# mipi_serializer1.net
KiCad netlist of a schematic drawn in Altium Designer
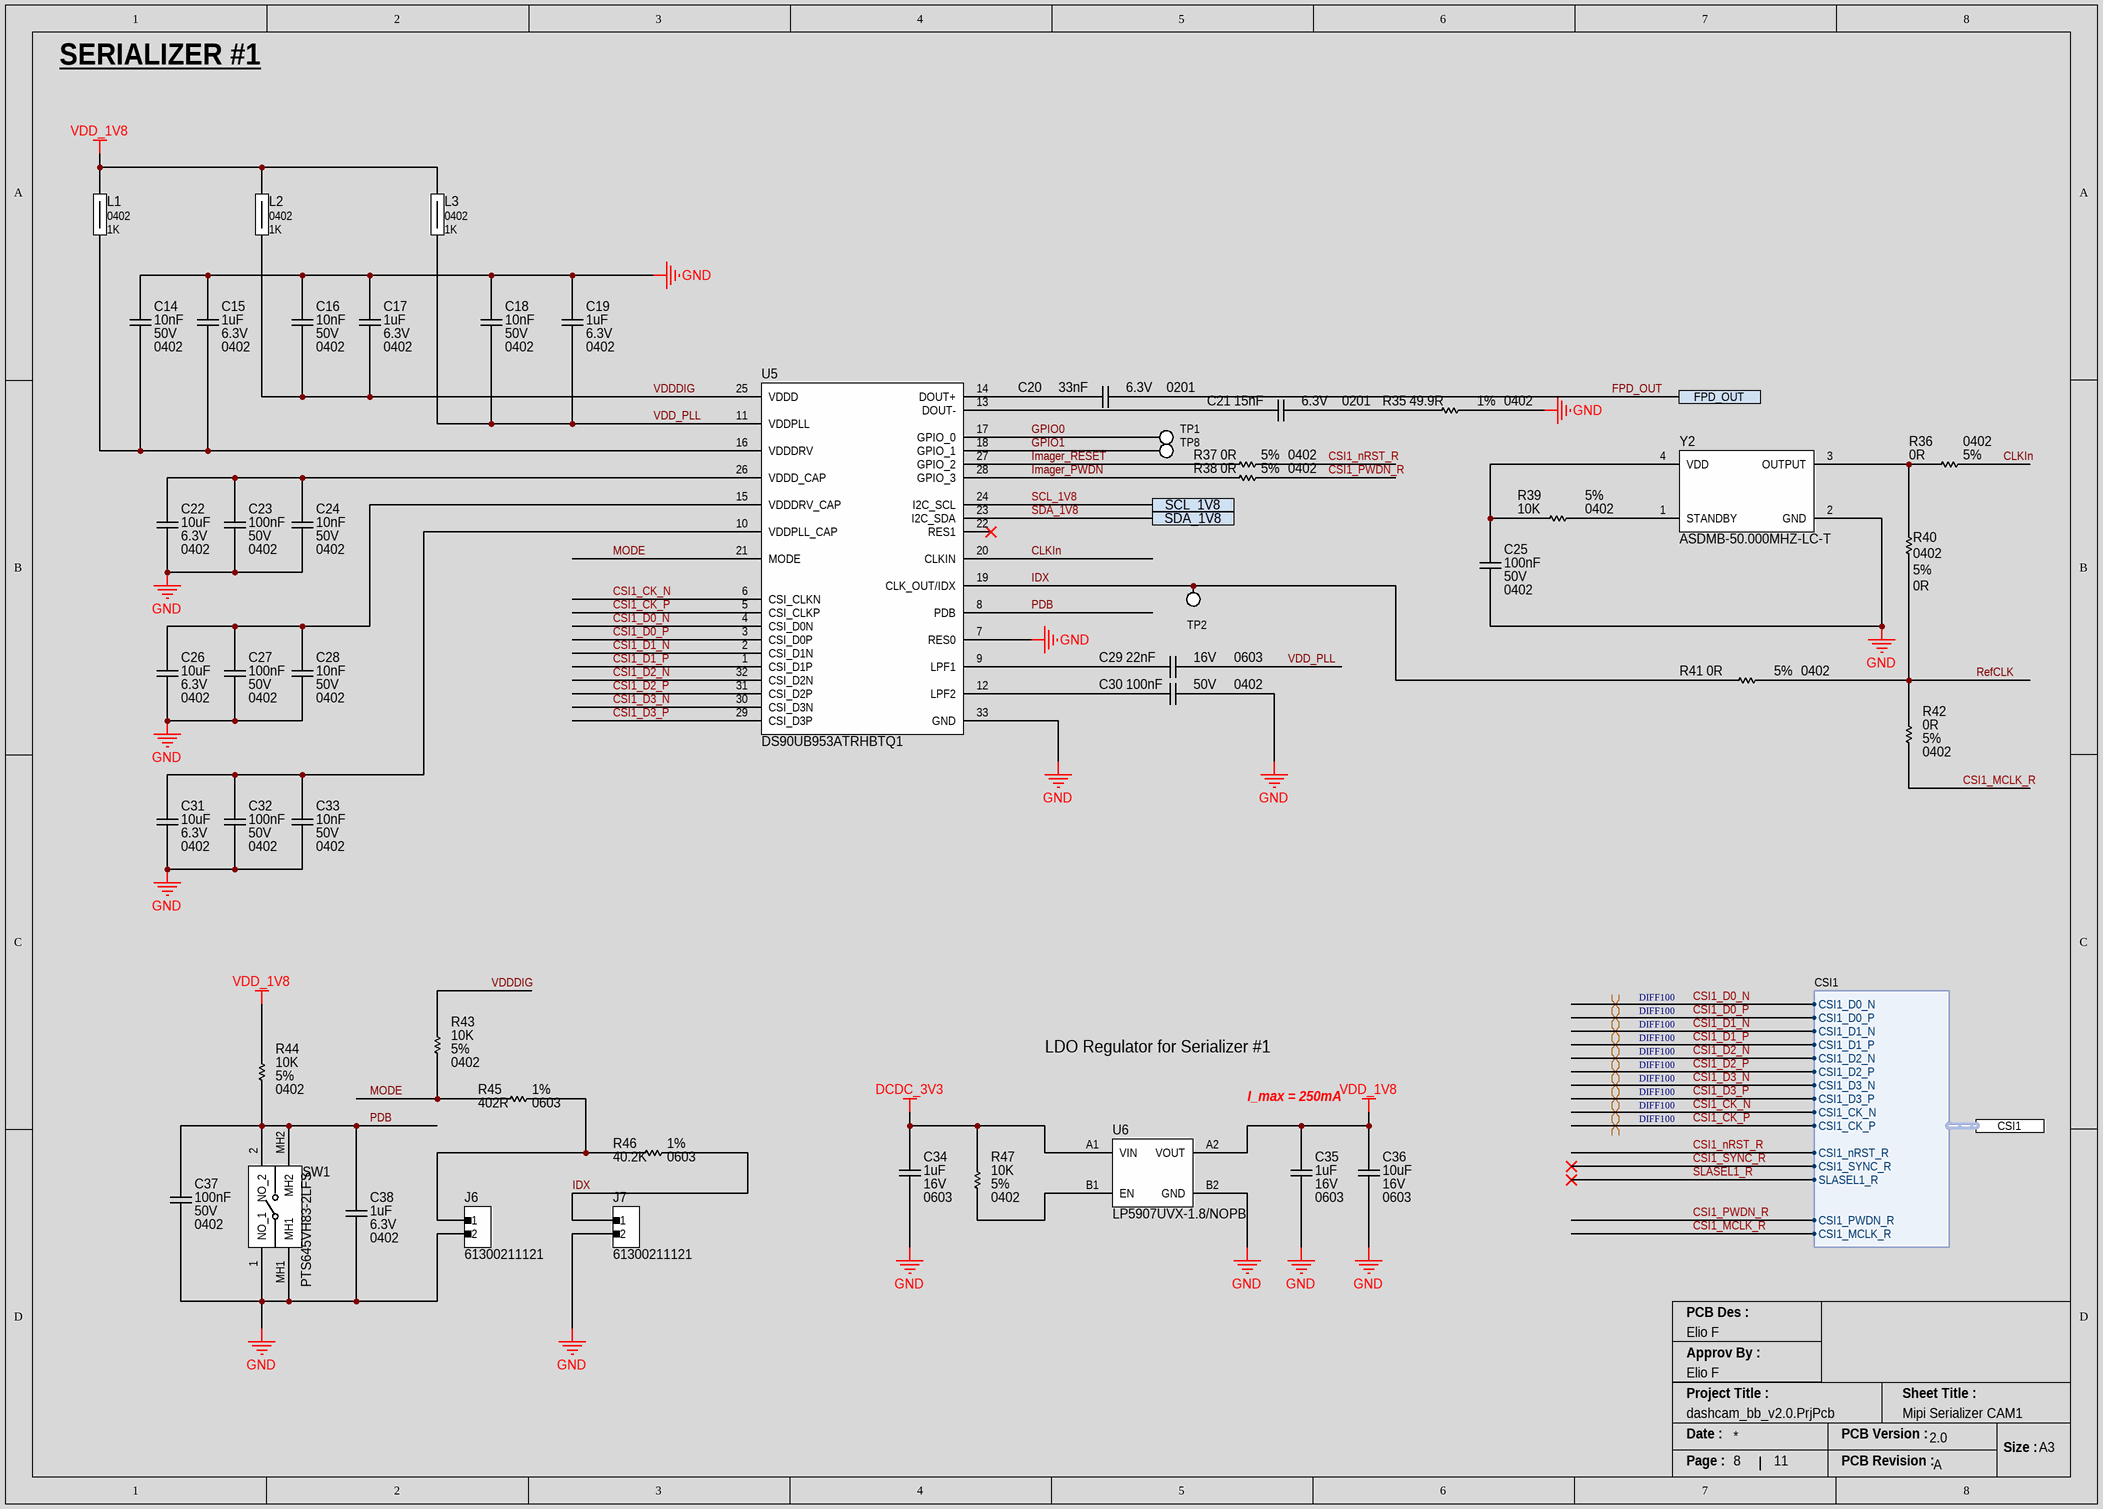
[diagram p0: mipi_serializer1.SchDoc]

(export (version "E")
  (design (tool "Eeschema 10.0.6"))
  (components
    (comp (ref "C14")
      (value "GRM155R71H103KA88D")
      (footprint "CAP_0402_CAPC1005X05N")
      (description "Multilayer Ceramic Capacitors MLCC Surface Mount 0402 0.01uF 50 Volts X7R 10%")
      (fields
        (field (name "MANUFACTURER") "Murata")
        (field (name "TOLERANCE") "10%")
        (field (name "VOLTAGE RATING") "50V")
        (field (name "CAPACITANCE") "10nF")
        (field (name "CASE/PACKAGE") "0402")
      )
      (libsource (lib "Electronic Devices_LIB") (part "CAP_10nF_50V_X7R_0402"))
    )
    (comp (ref "C15")
      (value "CL05B105KQ5NQNC")
      (footprint "CAP_0402_CAPC1005X05N")
      (description "Multilayer Ceramic Capacitor, 1 uF, 6.3 V, ï¿½ 10%, X7R, 0402 [1005 Metric]")
      (fields
        (field (name "MANUFACTURER") "Samsung")
        (field (name "TOLERANCE") "10%")
        (field (name "CAPACITANCE") "1uF")
        (field (name "VOLTAGE RATING") "6.3V")
        (field (name "CASE CODE (IMPERIAL)") "0402")
      )
      (libsource (lib "Electronic Devices_LIB") (part "CAP_1uF_6.3V_X7R_0402"))
    )
    (comp (ref "C16")
      (value "GRM155R71H103KA88D")
      (footprint "CAP_0402_CAPC1005X05N")
      (description "Multilayer Ceramic Capacitors MLCC Surface Mount 0402 0.01uF 50 Volts X7R 10%")
      (fields
        (field (name "MANUFACTURER") "Murata")
        (field (name "TOLERANCE") "10%")
        (field (name "VOLTAGE RATING") "50V")
        (field (name "CAPACITANCE") "10nF")
        (field (name "CASE/PACKAGE") "0402")
      )
      (libsource (lib "Electronic Devices_LIB") (part "CAP_10nF_50V_X7R_0402"))
    )
    (comp (ref "C17")
      (value "CL05B105KQ5NQNC")
      (footprint "CAP_0402_CAPC1005X05N")
      (description "Multilayer Ceramic Capacitor, 1 uF, 6.3 V, ï¿½ 10%, X7R, 0402 [1005 Metric]")
      (fields
        (field (name "MANUFACTURER") "Samsung")
        (field (name "TOLERANCE") "10%")
        (field (name "CAPACITANCE") "1uF")
        (field (name "VOLTAGE RATING") "6.3V")
        (field (name "CASE CODE (IMPERIAL)") "0402")
      )
      (libsource (lib "Electronic Devices_LIB") (part "CAP_1uF_6.3V_X7R_0402"))
    )
    (comp (ref "C18")
      (value "GRM155R71H103KA88D")
      (footprint "CAP_0402_CAPC1005X05N")
      (description "Multilayer Ceramic Capacitors MLCC Surface Mount 0402 0.01uF 50 Volts X7R 10%")
      (fields
        (field (name "MANUFACTURER") "Murata")
        (field (name "TOLERANCE") "10%")
        (field (name "VOLTAGE RATING") "50V")
        (field (name "CAPACITANCE") "10nF")
        (field (name "CASE/PACKAGE") "0402")
      )
      (libsource (lib "Electronic Devices_LIB") (part "CAP_10nF_50V_X7R_0402"))
    )
    (comp (ref "C19")
      (value "CL05B105KQ5NQNC")
      (footprint "CAP_0402_CAPC1005X05N")
      (description "Multilayer Ceramic Capacitor, 1 uF, 6.3 V, ï¿½ 10%, X7R, 0402 [1005 Metric]")
      (fields
        (field (name "MANUFACTURER") "Samsung")
        (field (name "TOLERANCE") "10%")
        (field (name "CAPACITANCE") "1uF")
        (field (name "VOLTAGE RATING") "6.3V")
        (field (name "CASE CODE (IMPERIAL)") "0402")
      )
      (libsource (lib "Electronic Devices_LIB") (part "CAP_1uF_6.3V_X7R_0402"))
    )
    (comp (ref "C20")
      (value "GRM033R60J333KE01D")
      (footprint "CAP_0201_CAPC0603X03N")
      (description "Multilayer Ceramic Capacitor, 0.033 uF, 6.3 V, ± 10%, X5R, 0201 [0603 Metric]")
      (fields
        (field (name "MANUFACTURER") "Murata")
        (field (name "TOLERANCE") "10%")
        (field (name "VOLTAGE RATING") "6.3V")
        (field (name "CAPACITANCE") "33nF")
        (field (name "CASE/PACKAGE") "0201")
      )
      (libsource (lib "Electronic Devices_LIB") (part "CAP_0.033uF_6.3V_X5R_0201"))
    )
    (comp (ref "C21")
      (value "GRM033R60J153KE01D")
      (footprint "CAP_0201_CAPC0603X03N")
      (description "0201 15 nF 6.3 V ±10% Tolerance X5R SMT Multilayer Ceramic Capacitor")
      (fields
        (field (name "MANUFACTURER") "Murata")
        (field (name "TOLERANCE") "10%")
        (field (name "VOLTAGE RATING") "6.3V")
        (field (name "CAPACITANCE") "15nF")
        (field (name "CASE/PACKAGE") "0201")
      )
      (libsource (lib "Electronic Devices_LIB") (part "CAP_0.015uF_6.3V_X5R_0201"))
    )
    (comp (ref "C22")
      (value "CL05A106MQ5NUNC")
      (footprint "CAP_0402_CAPC1005X05N")
      (description "Cap Ceramic 10uF 6.3V X5R 20% SMD 0402 85C T/R")
      (fields
        (field (name "MANUFACTURER") "Samsung")
        (field (name "TOLERANCE") "20%")
        (field (name "CASE/PACKAGE") "0402")
        (field (name "CAPACITANCE") "10uF")
        (field (name "VOLTAGE RATING") "6.3V")
      )
      (libsource (lib "Electronic Devices_LIB") (part "CAP_10UF_6.3V_X5R_0402"))
    )
    (comp (ref "C23")
      (value "GRM155R71H104KE14D")
      (footprint "CAP_0402_CAPC1005X05N")
      (description "Multilayer Ceramic Capacitor, 0.1 uF, 16 V, ± 10%, X7R, 0402 [1005 Metric]")
      (fields
        (field (name "MANUFACTURER") "Murata")
        (field (name "TOLERANCE") "10%")
        (field (name "VOLTAGE RATING") "50V")
        (field (name "CAPACITANCE") "100nF")
        (field (name "CASE/PACKAGE") "0402")
      )
      (libsource (lib "Electronic Devices_LIB") (part "CAP_100NF_50V_X7R_0402"))
    )
    (comp (ref "C24")
      (value "GRM155R71H103KA88D")
      (footprint "CAP_0402_CAPC1005X05N")
      (description "Multilayer Ceramic Capacitors MLCC Surface Mount 0402 0.01uF 50 Volts X7R 10%")
      (fields
        (field (name "MANUFACTURER") "Murata")
        (field (name "TOLERANCE") "10%")
        (field (name "VOLTAGE RATING") "50V")
        (field (name "CAPACITANCE") "10nF")
        (field (name "CASE/PACKAGE") "0402")
      )
      (libsource (lib "Electronic Devices_LIB") (part "CAP_10nF_50V_X7R_0402"))
    )
    (comp (ref "C25")
      (value "GRM155R71H104KE14D")
      (footprint "CAP_0402_CAPC1005X05N")
      (description "Multilayer Ceramic Capacitor, 0.1 uF, 16 V, ± 10%, X7R, 0402 [1005 Metric]")
      (fields
        (field (name "MANUFACTURER") "Murata")
        (field (name "TOLERANCE") "10%")
        (field (name "VOLTAGE RATING") "50V")
        (field (name "CAPACITANCE") "100nF")
        (field (name "CASE/PACKAGE") "0402")
      )
      (libsource (lib "Electronic Devices_LIB") (part "CAP_100NF_50V_X7R_0402"))
    )
    (comp (ref "C26")
      (value "CL05A106MQ5NUNC")
      (footprint "CAP_0402_CAPC1005X05N")
      (description "Cap Ceramic 10uF 6.3V X5R 20% SMD 0402 85C T/R")
      (fields
        (field (name "MANUFACTURER") "Samsung")
        (field (name "TOLERANCE") "20%")
        (field (name "CASE/PACKAGE") "0402")
        (field (name "CAPACITANCE") "10uF")
        (field (name "VOLTAGE RATING") "6.3V")
      )
      (libsource (lib "Electronic Devices_LIB") (part "CAP_10UF_6.3V_X5R_0402"))
    )
    (comp (ref "C27")
      (value "GRM155R71H104KE14D")
      (footprint "CAP_0402_CAPC1005X05N")
      (description "Multilayer Ceramic Capacitor, 0.1 uF, 16 V, ± 10%, X7R, 0402 [1005 Metric]")
      (fields
        (field (name "MANUFACTURER") "Murata")
        (field (name "TOLERANCE") "10%")
        (field (name "VOLTAGE RATING") "50V")
        (field (name "CAPACITANCE") "100nF")
        (field (name "CASE/PACKAGE") "0402")
      )
      (libsource (lib "Electronic Devices_LIB") (part "CAP_100NF_50V_X7R_0402"))
    )
    (comp (ref "C28")
      (value "GRM155R71H103KA88D")
      (footprint "CAP_0402_CAPC1005X05N")
      (description "Multilayer Ceramic Capacitors MLCC Surface Mount 0402 0.01uF 50 Volts X7R 10%")
      (fields
        (field (name "MANUFACTURER") "Murata")
        (field (name "TOLERANCE") "10%")
        (field (name "VOLTAGE RATING") "50V")
        (field (name "CAPACITANCE") "10nF")
        (field (name "CASE/PACKAGE") "0402")
      )
      (libsource (lib "Electronic Devices_LIB") (part "CAP_10nF_50V_X7R_0402"))
    )
    (comp (ref "C29")
      (value "C0603C223K4RACTU")
      (footprint "CAP_0603_CAPC1608X08N")
      (description "Multilayer Ceramic Capacitor, 0.022 uF, 16 V, ± 10%, X7R, 0603 [1608 Metric]")
      (fields
        (field (name "MANUFACTURER") "KEMET")
        (field (name "TOLERANCE") "10%")
        (field (name "VOLTAGE RATING (DC)") "16V")
        (field (name "CAPACITANCE") "22nF")
        (field (name "CASE/PACKAGE") "0603")
      )
      (libsource (lib "Electronic Devices_LIB") (part "CAP_22nF_16V_X7R_0603"))
    )
    (comp (ref "C30")
      (value "GRM155R71H104KE14D")
      (footprint "CAP_0402_CAPC1005X05N")
      (description "Multilayer Ceramic Capacitor, 0.1 uF, 16 V, ± 10%, X7R, 0402 [1005 Metric]")
      (fields
        (field (name "MANUFACTURER") "Murata")
        (field (name "TOLERANCE") "10%")
        (field (name "VOLTAGE RATING") "50V")
        (field (name "CAPACITANCE") "100nF")
        (field (name "CASE/PACKAGE") "0402")
      )
      (libsource (lib "Electronic Devices_LIB") (part "CAP_100NF_50V_X7R_0402"))
    )
    (comp (ref "C31")
      (value "CL05A106MQ5NUNC")
      (footprint "CAP_0402_CAPC1005X05N")
      (description "Cap Ceramic 10uF 6.3V X5R 20% SMD 0402 85C T/R")
      (fields
        (field (name "MANUFACTURER") "Samsung")
        (field (name "TOLERANCE") "20%")
        (field (name "CASE/PACKAGE") "0402")
        (field (name "CAPACITANCE") "10uF")
        (field (name "VOLTAGE RATING") "6.3V")
      )
      (libsource (lib "Electronic Devices_LIB") (part "CAP_10UF_6.3V_X5R_0402"))
    )
    (comp (ref "C32")
      (value "GRM155R71H104KE14D")
      (footprint "CAP_0402_CAPC1005X05N")
      (description "Multilayer Ceramic Capacitor, 0.1 uF, 16 V, ± 10%, X7R, 0402 [1005 Metric]")
      (fields
        (field (name "MANUFACTURER") "Murata")
        (field (name "TOLERANCE") "10%")
        (field (name "VOLTAGE RATING") "50V")
        (field (name "CAPACITANCE") "100nF")
        (field (name "CASE/PACKAGE") "0402")
      )
      (libsource (lib "Electronic Devices_LIB") (part "CAP_100NF_50V_X7R_0402"))
    )
    (comp (ref "C33")
      (value "GRM155R71H103KA88D")
      (footprint "CAP_0402_CAPC1005X05N")
      (description "Multilayer Ceramic Capacitors MLCC Surface Mount 0402 0.01uF 50 Volts X7R 10%")
      (fields
        (field (name "MANUFACTURER") "Murata")
        (field (name "TOLERANCE") "10%")
        (field (name "VOLTAGE RATING") "50V")
        (field (name "CAPACITANCE") "10nF")
        (field (name "CASE/PACKAGE") "0402")
      )
      (libsource (lib "Electronic Devices_LIB") (part "CAP_10nF_50V_X7R_0402"))
    )
    (comp (ref "C34")
      (value "CL10A105KO8NNNC")
      (footprint "CAP_0603_CAPC1608X08N")
      (description "CAP CER 1UF 16V X5R 0603")
      (fields
        (field (name "MANUFACTURER") "Samsung")
        (field (name "TOLERANCE") "10%")
        (field (name "VOLTAGE RATING") "16V")
        (field (name "CAPACITANCE") "1uF")
        (field (name "CASE/PACKAGE") "0603")
      )
      (libsource (lib "Electronic Devices_LIB") (part "CAP_1UF_16V_X5R_0603"))
    )
    (comp (ref "C35")
      (value "CL10A105KO8NNNC")
      (footprint "CAP_0603_CAPC1608X08N")
      (description "CAP CER 1UF 16V X5R 0603")
      (fields
        (field (name "MANUFACTURER") "Samsung")
        (field (name "TOLERANCE") "10%")
        (field (name "VOLTAGE RATING") "16V")
        (field (name "CAPACITANCE") "1uF")
        (field (name "CASE/PACKAGE") "0603")
      )
      (libsource (lib "Electronic Devices_LIB") (part "CAP_1UF_16V_X5R_0603"))
    )
    (comp (ref "C36")
      (value "GRM188R61C106MAALD")
      (footprint "CAP_0603_CAPC1608X08N")
      (description "0603 10 uF 16 V ±20% Tolerance X5R Multilayer Ceramic Chip Capacitor")
      (fields
        (field (name "MANUFACTURER") "Murata")
        (field (name "TOLERANCE") "20%")
        (field (name "VOLTAGE RATING") "16V")
        (field (name "CAPACITANCE") "10uF")
        (field (name "CASE/PACKAGE") "0603")
      )
      (libsource (lib "Electronic Devices_LIB") (part "CAP_10UF_16V_X5R_0603"))
    )
    (comp (ref "C37")
      (value "GRM155R71H104KE14D")
      (footprint "CAP_0402_CAPC1005X05N")
      (description "Multilayer Ceramic Capacitor, 0.1 uF, 16 V, ± 10%, X7R, 0402 [1005 Metric]")
      (fields
        (field (name "MANUFACTURER") "Murata")
        (field (name "TOLERANCE") "10%")
        (field (name "VOLTAGE RATING") "50V")
        (field (name "CAPACITANCE") "100nF")
        (field (name "CASE/PACKAGE") "0402")
      )
      (libsource (lib "Electronic Devices_LIB") (part "CAP_100NF_50V_X7R_0402"))
    )
    (comp (ref "C38")
      (value "CL05B105KQ5NQNC")
      (footprint "CAP_0402_CAPC1005X05N")
      (description "Multilayer Ceramic Capacitor, 1 uF, 6.3 V, ï¿½ 10%, X7R, 0402 [1005 Metric]")
      (fields
        (field (name "MANUFACTURER") "Samsung")
        (field (name "TOLERANCE") "10%")
        (field (name "CAPACITANCE") "1uF")
        (field (name "VOLTAGE RATING") "6.3V")
        (field (name "CASE CODE (IMPERIAL)") "0402")
      )
      (libsource (lib "Electronic Devices_LIB") (part "CAP_1uF_6.3V_X7R_0402"))
    )
    (comp (ref "J6")
      (value "61300211121")
      (footprint "HEADER_MALE_HDRV2W110P0X254_1X2_508X254X854P")
      (description "THT Vertical Pin Header WR-PHD, Pitch 2.54 mm, Single Row, 2 pins")
      (fields (field (name "MANUFACTURER") "Wurth Electronics"))
      (libsource (lib "Electronic Devices_LIB") (part "CONN_HEADER_MALE_2P_2.54_61300211121"))
    )
    (comp (ref "J7")
      (value "61300211121")
      (footprint "HEADER_MALE_HDRV2W110P0X254_1X2_508X254X854P")
      (description "THT Vertical Pin Header WR-PHD, Pitch 2.54 mm, Single Row, 2 pins")
      (fields (field (name "MANUFACTURER") "Wurth Electronics"))
      (libsource (lib "Electronic Devices_LIB") (part "CONN_HEADER_MALE_2P_2.54_61300211121"))
    )
    (comp (ref "L1")
      (value "*BLM15AX102SN1D")
      (footprint "IND_0402")
      (description "Ferrite Beads Multi-Layer 1KOhm 25% 100MHz 350mA 490mOhm DCR 0402 Paper T/R")
      (fields
        (field (name "MANUFACTURER") "Murata")
        (field (name "MANUFACTURER PART NUMBER") "BLM15AX102SN1D")
        (field (name "CASE/PACKAGE") "0402")
        (field (name "IMPEDANCE") "1K")
      )
      (libsource (lib "Electronic Devices_LIB") (part "IND_FERRITE_BEADS_1K_350mA_BLM15AX102SN1D"))
    )
    (comp (ref "L2")
      (value "*BLM15AX102SN1D")
      (footprint "IND_0402")
      (description "Ferrite Beads Multi-Layer 1KOhm 25% 100MHz 350mA 490mOhm DCR 0402 Paper T/R")
      (fields
        (field (name "MANUFACTURER") "Murata")
        (field (name "MANUFACTURER PART NUMBER") "BLM15AX102SN1D")
        (field (name "CASE/PACKAGE") "0402")
        (field (name "IMPEDANCE") "1K")
      )
      (libsource (lib "Electronic Devices_LIB") (part "IND_FERRITE_BEADS_1K_350mA_BLM15AX102SN1D"))
    )
    (comp (ref "L3")
      (value "*BLM15AX102SN1D")
      (footprint "IND_0402")
      (description "Ferrite Beads Multi-Layer 1KOhm 25% 100MHz 350mA 490mOhm DCR 0402 Paper T/R")
      (fields
        (field (name "MANUFACTURER") "Murata")
        (field (name "MANUFACTURER PART NUMBER") "BLM15AX102SN1D")
        (field (name "CASE/PACKAGE") "0402")
        (field (name "IMPEDANCE") "1K")
      )
      (libsource (lib "Electronic Devices_LIB") (part "IND_FERRITE_BEADS_1K_350mA_BLM15AX102SN1D"))
    )
    (comp (ref "R35")
      (value "CR0402-FX-49R9GLF")
      (footprint "RES_0402_RESC1005X04N")
      (description "SMD Chip Resistor, 49.9 Ohm, ± 1%, 63 mW, 0402 [1005 Metric], Thick Film, General Purpose")
      (fields
        (field (name "MANUFACTURER") "Bourns")
        (field (name "RESISTANCE") "49.9R")
        (field (name "TOLERANCE") "1%")
        (field (name "CASE/PACKAGE") "0402")
      )
      (libsource (lib "Electronic Devices_LIB") (part "RES_49.9R_1%_63mW_0402"))
    )
    (comp (ref "R36")
      (value "ERJ-2GE0R00X")
      (footprint "RES_0402_RESC1005X04N")
      (description "SMD Chip Resistor, Jumper, 0 ohm, 100 mW, 0402 [1005 Metric], Thick Film, General Purpose")
      (fields
        (field (name "MANUFACTURER") "Panasonic")
        (field (name "CASE CODE (IMPERIAL)") "0402")
        (field (name "TOLERANCE") "5%")
        (field (name "RESISTANCE") "0R")
      )
      (libsource (lib "Electronic Devices_LIB") (part "RES_0R_5%_100mW_0402"))
    )
    (comp (ref "R37")
      (value "ERJ-2GE0R00X")
      (footprint "RES_0402_RESC1005X04N")
      (description "SMD Chip Resistor, Jumper, 0 ohm, 100 mW, 0402 [1005 Metric], Thick Film, General Purpose")
      (fields
        (field (name "MANUFACTURER") "Panasonic")
        (field (name "CASE CODE (IMPERIAL)") "0402")
        (field (name "TOLERANCE") "5%")
        (field (name "RESISTANCE") "0R")
      )
      (libsource (lib "Electronic Devices_LIB") (part "RES_0R_5%_100mW_0402"))
    )
    (comp (ref "R38")
      (value "ERJ-2GE0R00X")
      (footprint "RES_0402_RESC1005X04N")
      (description "SMD Chip Resistor, Jumper, 0 ohm, 100 mW, 0402 [1005 Metric], Thick Film, General Purpose")
      (fields
        (field (name "MANUFACTURER") "Panasonic")
        (field (name "CASE CODE (IMPERIAL)") "0402")
        (field (name "TOLERANCE") "5%")
        (field (name "RESISTANCE") "0R")
      )
      (libsource (lib "Electronic Devices_LIB") (part "RES_0R_5%_100mW_0402"))
    )
    (comp (ref "R39")
      (value "ERJ-2GEJ103X")
      (footprint "RES_0402_RESC1005X04N")
      (description "Res Thick Film 0402 10K Ohm 5% 1/10W ±200ppm/°C Molded SMD Punched Carrier T/R")
      (fields
        (field (name "MANUFACTURER") "Panasonic")
        (field (name "TOLERANCE") "5%")
        (field (name "RESISTANCE") "10K")
        (field (name "CASE/PACKAGE") "0402")
      )
      (libsource (lib "Electronic Devices_LIB") (part "RES_10K_5%_100mW_0402"))
    )
    (comp (ref "R40")
      (value "ERJ-2GE0R00X")
      (footprint "RES_0402_RESC1005X04N")
      (description "SMD Chip Resistor, Jumper, 0 ohm, 100 mW, 0402 [1005 Metric], Thick Film, General Purpose")
      (fields
        (field (name "MANUFACTURER") "Panasonic")
        (field (name "CASE CODE (IMPERIAL)") "0402")
        (field (name "TOLERANCE") "5%")
        (field (name "RESISTANCE") "0R")
      )
      (libsource (lib "Electronic Devices_LIB") (part "RES_0R_5%_100mW_0402"))
    )
    (comp (ref "R41")
      (value "ERJ-2GE0R00X")
      (footprint "RES_0402_RESC1005X04N")
      (description "SMD Chip Resistor, Jumper, 0 ohm, 100 mW, 0402 [1005 Metric], Thick Film, General Purpose")
      (fields
        (field (name "MANUFACTURER") "Panasonic")
        (field (name "CASE CODE (IMPERIAL)") "0402")
        (field (name "TOLERANCE") "5%")
        (field (name "RESISTANCE") "0R")
      )
      (libsource (lib "Electronic Devices_LIB") (part "RES_0R_5%_100mW_0402"))
    )
    (comp (ref "R42")
      (value "ERJ-2GE0R00X")
      (footprint "RES_0402_RESC1005X04N")
      (description "SMD Chip Resistor, Jumper, 0 ohm, 100 mW, 0402 [1005 Metric], Thick Film, General Purpose")
      (fields
        (field (name "MANUFACTURER") "Panasonic")
        (field (name "CASE CODE (IMPERIAL)") "0402")
        (field (name "TOLERANCE") "5%")
        (field (name "RESISTANCE") "0R")
      )
      (libsource (lib "Electronic Devices_LIB") (part "RES_0R_5%_100mW_0402"))
    )
    (comp (ref "R43")
      (value "ERJ-2GEJ103X")
      (footprint "RES_0402_RESC1005X04N")
      (description "Res Thick Film 0402 10K Ohm 5% 1/10W ±200ppm/°C Molded SMD Punched Carrier T/R")
      (fields
        (field (name "MANUFACTURER") "Panasonic")
        (field (name "TOLERANCE") "5%")
        (field (name "RESISTANCE") "10K")
        (field (name "CASE/PACKAGE") "0402")
      )
      (libsource (lib "Electronic Devices_LIB") (part "RES_10K_5%_100mW_0402"))
    )
    (comp (ref "R44")
      (value "ERJ-2GEJ103X")
      (footprint "RES_0402_RESC1005X04N")
      (description "Res Thick Film 0402 10K Ohm 5% 1/10W ±200ppm/°C Molded SMD Punched Carrier T/R")
      (fields
        (field (name "MANUFACTURER") "Panasonic")
        (field (name "TOLERANCE") "5%")
        (field (name "RESISTANCE") "10K")
        (field (name "CASE/PACKAGE") "0402")
      )
      (libsource (lib "Electronic Devices_LIB") (part "RES_10K_5%_100mW_0402"))
    )
    (comp (ref "R45")
      (value "CRCW0603402RFKEA")
      (footprint "RES_0603_RESC1608X04N")
      (description "CRCW Series 0603 0.1 W 402 Ohm ±1 % ±100 ppm/K SMT Thick Film Chip Resistor")
      (fields
        (field (name "MANUFACTURER") "Vishay")
        (field (name "TOLERANCE") "1%")
        (field (name "RESISTANCE") "402R")
        (field (name "CASE/PACKAGE") "0603")
      )
      (libsource (lib "Electronic Devices_LIB") (part "RES_402R_1%_100mW_0402"))
    )
    (comp (ref "R46")
      (value "RC0603FR-0740K2L")
      (footprint "RES_0603_RESC1608X04N")
      (description "Res General Purpose Thick Film 0603 40.2K Ohm 1% 1/10W ±100ppm/°C Molded SMD Paper T/R")
      (fields
        (field (name "MANUFACTURER") "Yageo")
        (field (name "TOLERANCE") "1%")
        (field (name "RESISTANCE") "40.2K")
        (field (name "CASE/PACKAGE") "0603")
      )
      (libsource (lib "Electronic Devices_LIB") (part "RES_40.2K_1%_100mW_0603"))
    )
    (comp (ref "R47")
      (value "ERJ-2GEJ103X")
      (footprint "RES_0402_RESC1005X04N")
      (description "Res Thick Film 0402 10K Ohm 5% 1/10W ±200ppm/°C Molded SMD Punched Carrier T/R")
      (fields
        (field (name "MANUFACTURER") "Panasonic")
        (field (name "TOLERANCE") "5%")
        (field (name "RESISTANCE") "10K")
        (field (name "CASE/PACKAGE") "0402")
      )
      (libsource (lib "Electronic Devices_LIB") (part "RES_10K_5%_100mW_0402"))
    )
    (comp (ref "SW1")
      (value "PTS645VH83-2LFS")
      (footprint "SW_RA_PTS645VH832LFS")
      (description "Switch Tactile N.O SPST Round Button PC Pins 0.05A 12VDC 100000Cycle 1.96N Thru-Hole Bulk")
      (fields (field (name "MANUFACTURER") "ITT C&K"))
      (libsource (lib "Electronic Devices_LIB") (part "SWITCH_SPST_NO_RA_PTS645VH83-2LFS"))
    )
    (comp (ref "TP1")
      (value "NO COMPONENT")
      (footprint "TP_PAD_1.6MM_SMD_ROUND")
      (description "Test Point, SMD pad, round, 1.5mm, 1.6mm, 3mm diameter")
      (libsource (lib "Electronic Devices_LIB") (part "TP_PAD_SMD_Round"))
    )
    (comp (ref "TP2")
      (value "NO COMPONENT")
      (footprint "TP_PAD_1.6MM_SMD_ROUND")
      (description "Test Point, SMD pad, round, 1.5mm, 1.6mm, 3mm diameter")
      (libsource (lib "Electronic Devices_LIB") (part "TP_PAD_SMD_Round"))
    )
    (comp (ref "TP8")
      (value "NO COMPONENT")
      (footprint "TP_PAD_1.6MM_SMD_ROUND")
      (description "Test Point, SMD pad, round, 1.5mm, 1.6mm, 3mm diameter")
      (libsource (lib "Electronic Devices_LIB") (part "TP_PAD_SMD_Round"))
    )
    (comp (ref "U5")
      (value "DS90UB953ATRHBTQ1")
      (footprint "IC_SERIALIZER_QFN50P500X500X100-33N-D")
      (description "FPD-Link III 4.16-Gbps serializer with CSI-2 interface 32-VQFN -40 to 125")
      (fields (field (name "MANUFACTURER") "Texas Instruments"))
      (libsource (lib "Electronic Devices_LIB") (part "IC_MIPI_SERIALIZER_DS90UB953ATRHBTQ1"))
    )
    (comp (ref "U6")
      (value "LP5907UVX-1.8/NOPB")
      (footprint "IC_REG_LDO_BGA4C35P2X2_71X71X40")
      (description "Low Dropout Regulators(LDO) Positive Fixed 200mV @ 250mA 5.5V 1.8V 250mA DSBGA-4 RoHS")
      (fields (field (name "MANUFACTURER") "Texas Instruments"))
      (libsource (lib "Electronic Devices_LIB") (part "IC_REG_LDO_1.8V_250mA_LP5907UVX-1.8/NOPB"))
    )
    (comp (ref "Y2")
      (value "ASDMB-50.000MHZ-LC-T")
      (footprint "XTAL_ASDMB-50.000MHZ-LC-T")
      (fields (field (name "MANUFACTURER") "Abracon"))
      (libsource (lib "Electronic Devices_LIB") (part "CRYSTAL_ABRACON_50MHz_ASDMB-50.000MHZ-LC-T"))
    )
  )
  (nets
    (net (code "2") (name "/CLKIn") (class "Default")
      (node (ref "R36") (pin "2") (pinfunction "2_2") (pintype "passive"))
      (node (ref "U5") (pin "20") (pinfunction "CLKIN_20") (pintype "passive"))
    )
    (net (code "3") (name "/CSI1_CK_N") (class "Default")
      (node (ref "U5") (pin "6") (pinfunction "CSI_CLKN_6") (pintype "passive"))
    )
    (net (code "4") (name "/CSI1_CK_P") (class "Default")
      (node (ref "U5") (pin "5") (pinfunction "CSI_CLKP_5") (pintype "passive"))
    )
    (net (code "5") (name "/CSI1_D0_N") (class "Default")
      (node (ref "U5") (pin "4") (pinfunction "CSI_D0N_4") (pintype "passive"))
    )
    (net (code "6") (name "/CSI1_D0_P") (class "Default")
      (node (ref "U5") (pin "3") (pinfunction "CSI_D0P_3") (pintype "passive"))
    )
    (net (code "7") (name "/CSI1_D1_N") (class "Default")
      (node (ref "U5") (pin "2") (pinfunction "CSI_D1N_2") (pintype "passive"))
    )
    (net (code "8") (name "/CSI1_D1_P") (class "Default")
      (node (ref "U5") (pin "1") (pinfunction "CSI_D1P_1") (pintype "passive"))
    )
    (net (code "9") (name "/CSI1_D2_N") (class "Default")
      (node (ref "U5") (pin "32") (pinfunction "CSI_D2N_32") (pintype "passive"))
    )
    (net (code "10") (name "/CSI1_D2_P") (class "Default")
      (node (ref "U5") (pin "31") (pinfunction "CSI_D2P_31") (pintype "passive"))
    )
    (net (code "11") (name "/CSI1_D3_N") (class "Default")
      (node (ref "U5") (pin "30") (pinfunction "CSI_D3N_30") (pintype "passive"))
    )
    (net (code "12") (name "/CSI1_D3_P") (class "Default")
      (node (ref "U5") (pin "29") (pinfunction "CSI_D3P_29") (pintype "passive"))
    )
    (net (code "13") (name "/CSI1_MCLK_R") (class "Default")
      (node (ref "R42") (pin "1") (pinfunction "1_1") (pintype "passive"))
    )
    (net (code "14") (name "/CSI1_PWDN_R") (class "Default")
      (node (ref "R38") (pin "2") (pinfunction "2_2") (pintype "passive"))
    )
    (net (code "16") (name "/CSI1_nRST_R") (class "Default")
      (node (ref "R37") (pin "2") (pinfunction "2_2") (pintype "passive"))
    )
    (net (code "17") (name "/FPD_OUT") (class "Default")
      (node (ref "C20") (pin "2") (pinfunction "2_2") (pintype "passive"))
    )
    (net (code "18") (name "/GPIO0") (class "Default")
      (node (ref "TP1") (pin "1") (pinfunction "1_1") (pintype "passive"))
      (node (ref "U5") (pin "17") (pinfunction "GPIO_0_17") (pintype "passive"))
    )
    (net (code "19") (name "/GPIO1") (class "Default")
      (node (ref "TP8") (pin "1") (pinfunction "1_1") (pintype "passive"))
      (node (ref "U5") (pin "18") (pinfunction "GPIO_1_18") (pintype "passive"))
    )
    (net (code "20") (name "/IDX") (class "Default")
      (node (ref "J7") (pin "1") (pinfunction "1_1") (pintype "passive"))
      (node (ref "R41") (pin "2") (pinfunction "2_2") (pintype "passive"))
      (node (ref "R46") (pin "2") (pinfunction "2_2") (pintype "passive"))
      (node (ref "TP2") (pin "1") (pinfunction "1_1") (pintype "passive"))
      (node (ref "U5") (pin "19") (pinfunction "CLK_OUT/IDX_19") (pintype "passive"))
    )
    (net (code "21") (name "/Imager_PWDN") (class "Default")
      (node (ref "R38") (pin "1") (pinfunction "1_1") (pintype "passive"))
      (node (ref "U5") (pin "28") (pinfunction "GPIO_3_28") (pintype "passive"))
    )
    (net (code "22") (name "/Imager_RESET") (class "Default")
      (node (ref "R37") (pin "1") (pinfunction "1_1") (pintype "passive"))
      (node (ref "U5") (pin "27") (pinfunction "GPIO_2_27") (pintype "passive"))
    )
    (net (code "23") (name "/MODE") (class "Default")
      (node (ref "R43") (pin "1") (pinfunction "1_1") (pintype "passive"))
      (node (ref "R45") (pin "1") (pinfunction "1_1") (pintype "passive"))
      (node (ref "U5") (pin "21") (pinfunction "MODE_21") (pintype "passive"))
    )
    (net (code "24") (name "/PDB") (class "Default")
      (node (ref "C37") (pin "2") (pinfunction "2_2") (pintype "passive"))
      (node (ref "C38") (pin "2") (pinfunction "2_2") (pintype "passive"))
      (node (ref "R44") (pin "1") (pinfunction "1_1") (pintype "passive"))
      (node (ref "SW1") (pin "2") (pinfunction "NO_2_2") (pintype "passive"))
      (node (ref "SW1") (pin "MH2") (pinfunction "MH2_MH2") (pintype "passive"))
      (node (ref "U5") (pin "8") (pinfunction "PDB_8") (pintype "passive"))
    )
    (net (code "25") (name "/RefCLK") (class "Default")
      (node (ref "R40") (pin "1") (pinfunction "1_1") (pintype "passive"))
      (node (ref "R41") (pin "1") (pinfunction "1_1") (pintype "passive"))
      (node (ref "R42") (pin "2") (pinfunction "2_2") (pintype "passive"))
    )
    (net (code "26") (name "/SCL_1V8") (class "Default")
      (node (ref "U5") (pin "24") (pinfunction "I2C_SCL_24") (pintype "passive"))
    )
    (net (code "27") (name "/SDA_1V8") (class "Default")
      (node (ref "U5") (pin "23") (pinfunction "I2C_SDA_23") (pintype "passive"))
    )
    (net (code "29") (name "/VDDDIG") (class "Default")
      (node (ref "C16") (pin "1") (pinfunction "1_1") (pintype "passive"))
      (node (ref "C17") (pin "1") (pinfunction "1_1") (pintype "passive"))
      (node (ref "L2") (pin "1") (pinfunction "1_1") (pintype "passive"))
      (node (ref "R43") (pin "2") (pinfunction "2_2") (pintype "passive"))
      (node (ref "U5") (pin "25") (pinfunction "VDDD_25") (pintype "passive"))
    )
    (net (code "30") (name "/VDD_PLL") (class "Default")
      (node (ref "C18") (pin "1") (pinfunction "1_1") (pintype "passive"))
      (node (ref "C19") (pin "1") (pinfunction "1_1") (pintype "passive"))
      (node (ref "C29") (pin "2") (pinfunction "2_2") (pintype "passive"))
      (node (ref "L3") (pin "1") (pinfunction "1_1") (pintype "passive"))
      (node (ref "U5") (pin "11") (pinfunction "VDDPLL_11") (pintype "passive"))
    )
    (net (code "32") (name "DCDC_3V3") (class "Default")
      (node (ref "C34") (pin "2") (pinfunction "2_2") (pintype "passive"))
      (node (ref "R47") (pin "2") (pinfunction "2_2") (pintype "passive"))
      (node (ref "U6") (pin "A1") (pinfunction "VIN_A1") (pintype "passive"))
    )
    (net (code "33") (name "GND") (class "Default")
      (node (ref "C14") (pin "2") (pinfunction "2_2") (pintype "passive"))
      (node (ref "C15") (pin "2") (pinfunction "2_2") (pintype "passive"))
      (node (ref "C16") (pin "2") (pinfunction "2_2") (pintype "passive"))
      (node (ref "C17") (pin "2") (pinfunction "2_2") (pintype "passive"))
      (node (ref "C18") (pin "2") (pinfunction "2_2") (pintype "passive"))
      (node (ref "C19") (pin "2") (pinfunction "2_2") (pintype "passive"))
      (node (ref "C22") (pin "1") (pinfunction "1_1") (pintype "passive"))
      (node (ref "C23") (pin "1") (pinfunction "1_1") (pintype "passive"))
      (node (ref "C24") (pin "1") (pinfunction "1_1") (pintype "passive"))
      (node (ref "C25") (pin "1") (pinfunction "1_1") (pintype "passive"))
      (node (ref "C26") (pin "1") (pinfunction "1_1") (pintype "passive"))
      (node (ref "C27") (pin "1") (pinfunction "1_1") (pintype "passive"))
      (node (ref "C28") (pin "1") (pinfunction "1_1") (pintype "passive"))
      (node (ref "C30") (pin "1") (pinfunction "1_1") (pintype "passive"))
      (node (ref "C31") (pin "1") (pinfunction "1_1") (pintype "passive"))
      (node (ref "C32") (pin "1") (pinfunction "1_1") (pintype "passive"))
      (node (ref "C33") (pin "1") (pinfunction "1_1") (pintype "passive"))
      (node (ref "C34") (pin "1") (pinfunction "1_1") (pintype "passive"))
      (node (ref "C35") (pin "1") (pinfunction "1_1") (pintype "passive"))
      (node (ref "C36") (pin "1") (pinfunction "1_1") (pintype "passive"))
      (node (ref "C37") (pin "1") (pinfunction "1_1") (pintype "passive"))
      (node (ref "C38") (pin "1") (pinfunction "1_1") (pintype "passive"))
      (node (ref "J6") (pin "2") (pinfunction "2_2") (pintype "passive"))
      (node (ref "J7") (pin "2") (pinfunction "2_2") (pintype "passive"))
      (node (ref "R35") (pin "2") (pinfunction "2_2") (pintype "passive"))
      (node (ref "SW1") (pin "1") (pinfunction "NO_1_1") (pintype "passive"))
      (node (ref "SW1") (pin "MH1") (pinfunction "MH1_MH1") (pintype "passive"))
      (node (ref "U5") (pin "33") (pinfunction "GND_33") (pintype "passive"))
      (node (ref "U5") (pin "7") (pinfunction "RES0_7") (pintype "passive"))
      (node (ref "U6") (pin "B2") (pinfunction "GND_B2") (pintype "passive"))
      (node (ref "Y2") (pin "2") (pinfunction "GND_2") (pintype "power_in"))
    )
    (net (code "34") (name "Net-(C21-Pad2)") (class "Default")
      (node (ref "C21") (pin "2") (pinfunction "2_2") (pintype "passive"))
      (node (ref "R35") (pin "1") (pinfunction "1_1") (pintype "passive"))
    )
    (net (code "35") (name "Net-(J6-Pad1)") (class "Default")
      (node (ref "J6") (pin "1") (pinfunction "1_1") (pintype "passive"))
      (node (ref "R45") (pin "2") (pinfunction "2_2") (pintype "passive"))
      (node (ref "R46") (pin "1") (pinfunction "1_1") (pintype "passive"))
    )
    (net (code "36") (name "Net-(U5-DOUT+)") (class "Default")
      (node (ref "C20") (pin "1") (pinfunction "1_1") (pintype "passive"))
      (node (ref "U5") (pin "14") (pinfunction "DOUT+_14") (pintype "passive"))
    )
    (net (code "37") (name "Net-(U5-DOUT-)") (class "Default")
      (node (ref "C21") (pin "1") (pinfunction "1_1") (pintype "passive"))
      (node (ref "U5") (pin "13") (pinfunction "DOUT-_13") (pintype "passive"))
    )
    (net (code "38") (name "Net-(U5-LPF1)") (class "Default")
      (node (ref "C29") (pin "1") (pinfunction "1_1") (pintype "passive"))
      (node (ref "U5") (pin "9") (pinfunction "LPF1_9") (pintype "passive"))
    )
    (net (code "39") (name "Net-(U5-LPF2)") (class "Default")
      (node (ref "C30") (pin "2") (pinfunction "2_2") (pintype "passive"))
      (node (ref "U5") (pin "12") (pinfunction "LPF2_12") (pintype "passive"))
    )
    (net (code "40") (name "Net-(U5-VDDDRV)") (class "Default")
      (node (ref "C14") (pin "1") (pinfunction "1_1") (pintype "passive"))
      (node (ref "C15") (pin "1") (pinfunction "1_1") (pintype "passive"))
      (node (ref "L1") (pin "1") (pinfunction "1_1") (pintype "passive"))
      (node (ref "U5") (pin "16") (pinfunction "VDDDRV_16") (pintype "passive"))
    )
    (net (code "41") (name "Net-(U5-VDDDRV_CAP)") (class "Default")
      (node (ref "C26") (pin "2") (pinfunction "2_2") (pintype "passive"))
      (node (ref "C27") (pin "2") (pinfunction "2_2") (pintype "passive"))
      (node (ref "C28") (pin "2") (pinfunction "2_2") (pintype "passive"))
      (node (ref "U5") (pin "15") (pinfunction "VDDDRV_CAP_15") (pintype "passive"))
    )
    (net (code "42") (name "Net-(U5-VDDD_CAP)") (class "Default")
      (node (ref "C22") (pin "2") (pinfunction "2_2") (pintype "passive"))
      (node (ref "C23") (pin "2") (pinfunction "2_2") (pintype "passive"))
      (node (ref "C24") (pin "2") (pinfunction "2_2") (pintype "passive"))
      (node (ref "U5") (pin "26") (pinfunction "VDDD_CAP_26") (pintype "passive"))
    )
    (net (code "43") (name "Net-(U5-VDDPLL_CAP)") (class "Default")
      (node (ref "C31") (pin "2") (pinfunction "2_2") (pintype "passive"))
      (node (ref "C32") (pin "2") (pinfunction "2_2") (pintype "passive"))
      (node (ref "C33") (pin "2") (pinfunction "2_2") (pintype "passive"))
      (node (ref "U5") (pin "10") (pinfunction "VDDPLL_CAP_10") (pintype "passive"))
    )
    (net (code "44") (name "Net-(U6-EN)") (class "Default")
      (node (ref "R47") (pin "1") (pinfunction "1_1") (pintype "passive"))
      (node (ref "U6") (pin "B1") (pinfunction "EN_B1") (pintype "passive"))
    )
    (net (code "45") (name "Net-(Y2-OUTPUT)") (class "Default")
      (node (ref "R36") (pin "1") (pinfunction "1_1") (pintype "passive"))
      (node (ref "R40") (pin "2") (pinfunction "2_2") (pintype "passive"))
      (node (ref "Y2") (pin "3") (pinfunction "OUTPUT_3") (pintype "passive"))
    )
    (net (code "46") (name "Net-(Y2-STANDBY)") (class "Default")
      (node (ref "R39") (pin "2") (pinfunction "2_2") (pintype "passive"))
      (node (ref "Y2") (pin "1") (pinfunction "STANDBY_1") (pintype "passive"))
    )
    (net (code "47") (name "Net-(Y2-VDD)") (class "Default")
      (node (ref "C25") (pin "2") (pinfunction "2_2") (pintype "passive"))
      (node (ref "R39") (pin "1") (pinfunction "1_1") (pintype "passive"))
      (node (ref "Y2") (pin "4") (pinfunction "VDD_4") (pintype "power_in"))
    )
    (net (code "48") (name "VDD_1V8") (class "Default")
      (node (ref "C35") (pin "2") (pinfunction "2_2") (pintype "passive"))
      (node (ref "C36") (pin "2") (pinfunction "2_2") (pintype "passive"))
      (node (ref "L1") (pin "2") (pinfunction "2_2") (pintype "passive"))
      (node (ref "L2") (pin "2") (pinfunction "2_2") (pintype "passive"))
      (node (ref "L3") (pin "2") (pinfunction "2_2") (pintype "passive"))
      (node (ref "R44") (pin "2") (pinfunction "2_2") (pintype "passive"))
      (node (ref "U6") (pin "A2") (pinfunction "VOUT_A2") (pintype "passive"))
    )
    (net (code "49") (name "unconnected-(U5-RES1-Pad22)") (class "Default")
      (node (ref "U5") (pin "22") (pinfunction "RES1_22") (pintype "passive+no_connect"))
    )
  )
)
